# M8_AUX_CONN.net
KiCad netlist of a schematic drawn in Altium Designer
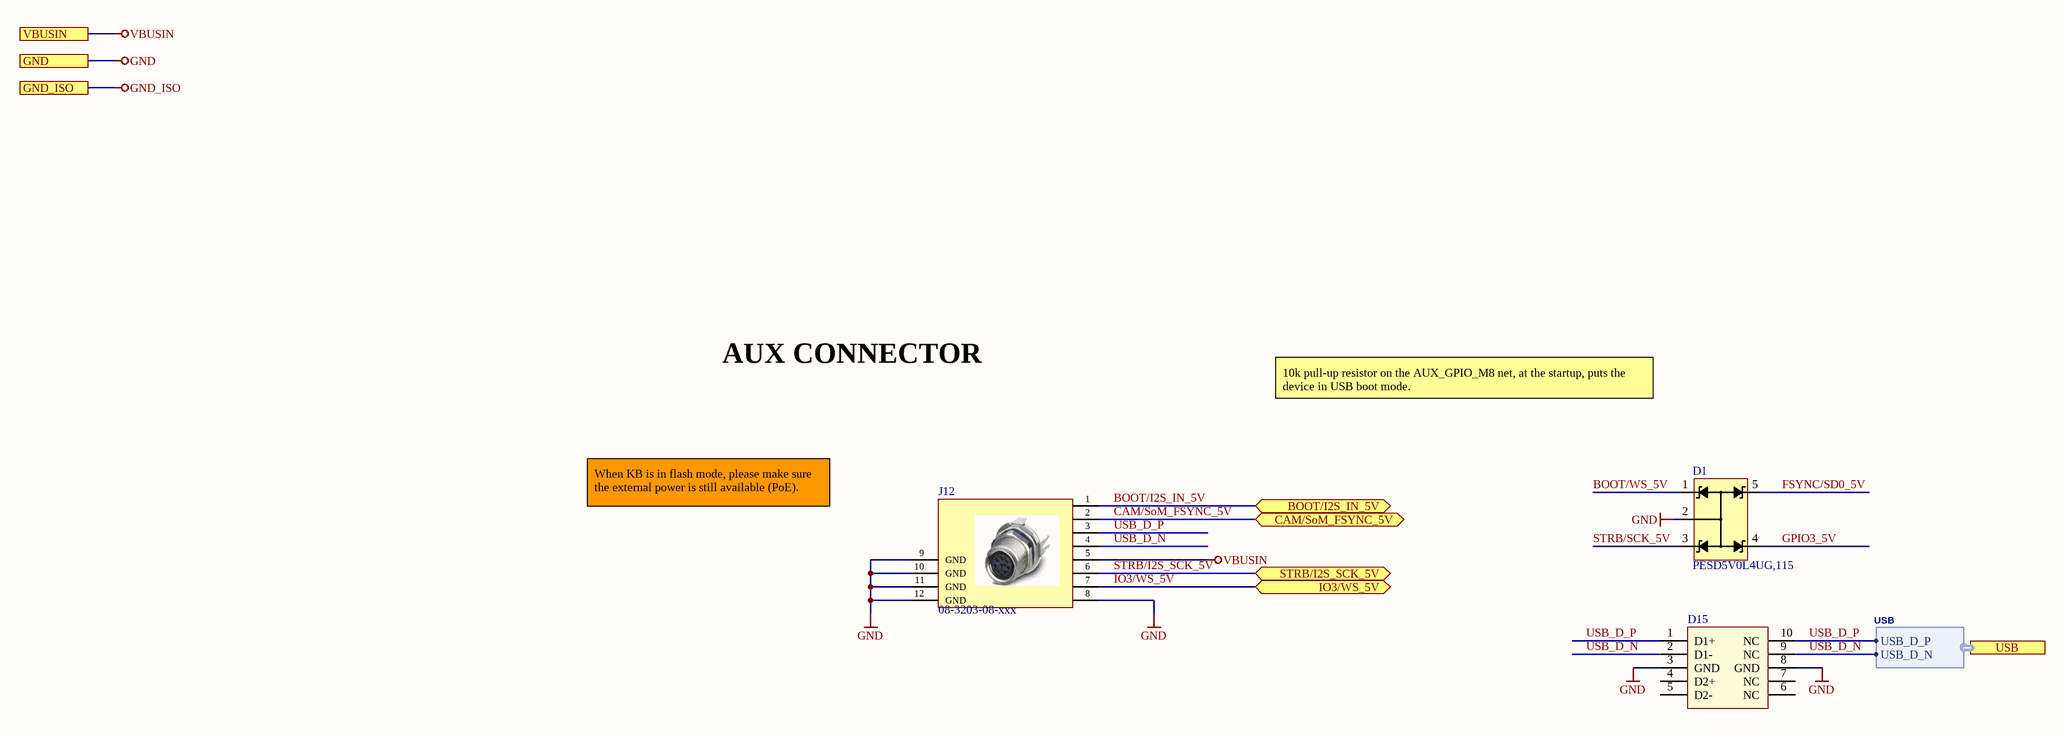
[diagram p0: M8_AUX_CONN.SchDoc]

(export (version "E")
  (design (tool "Eeschema 10.0.6"))
  (components
    (comp (ref "D1")
      (value "PESD5V0L4UG,115")
      (footprint "PESD3V3L4UG,115")
      (description "TVS DIODE 5V 12V 5TSSOP")
      (libsource (lib "Luxonis LLC") (part "PESD5V0L4UG,115"))
    )
    (comp (ref "D15")
      (value "TPD4EUSB30DQAR")
      (footprint "TPD4EUSB30DQAR")
      (description "TVS DIODE 5.5V 8V 10SON 8V Clamp 1A (8/20µs) Ipp Tvs Diode Surface Mount 10-USON (2.5x1)")
      (libsource (lib "Luxonis LLC") (part "TPD4EUSB30DQAR"))
    )
    (comp (ref "J12")
      (value "08-3203-08-xxx")
      (footprint "08-3203-08-XXX")
      (description "M8 Circular Connector")
      (libsource (lib "Luxonis LLC") (part "08-3203-08-xxx"))
    )
  )
  (nets
    (net (code "2") (name "/BOOT{slash}I2S_IN_5V") (class "Default")
      (node (ref "J12") (pin "1") (pinfunction "1_1") (pintype "passive"))
    )
    (net (code "3") (name "/BOOT{slash}WS_5V") (class "Default")
      (node (ref "D1") (pin "1") (pinfunction "1_1") (pintype "passive"))
    )
    (net (code "4") (name "/CAM{slash}SoM_FSYNC_5V") (class "Default")
      (node (ref "J12") (pin "2") (pinfunction "2_2") (pintype "passive"))
    )
    (net (code "5") (name "/FSYNC{slash}SD0_5V") (class "Default")
      (node (ref "D1") (pin "5") (pinfunction "5_5") (pintype "passive"))
    )
    (net (code "6") (name "/GPIO3_5V") (class "Default")
      (node (ref "D1") (pin "4") (pinfunction "4_4") (pintype "passive"))
    )
    (net (code "7") (name "/IO3{slash}WS_5V") (class "Default")
      (node (ref "J12") (pin "7") (pinfunction "7_7") (pintype "passive"))
    )
    (net (code "8") (name "/STRB{slash}I2S_SCK_5V") (class "Default")
      (node (ref "J12") (pin "6") (pinfunction "6_6") (pintype "passive"))
    )
    (net (code "9") (name "/STRB{slash}SCK_5V") (class "Default")
      (node (ref "D1") (pin "3") (pinfunction "3_3") (pintype "passive"))
    )
    (net (code "10") (name "/USB_D_N") (class "Default")
      (node (ref "D15") (pin "2") (pinfunction "D1-_2") (pintype "passive"))
      (node (ref "D15") (pin "9") (pinfunction "NC_9") (pintype "passive"))
      (node (ref "J12") (pin "4") (pinfunction "4_4") (pintype "passive"))
    )
    (net (code "11") (name "/USB_D_P") (class "Default")
      (node (ref "D15") (pin "1") (pinfunction "D1+_1") (pintype "passive"))
      (node (ref "D15") (pin "10") (pinfunction "NC_10") (pintype "passive"))
      (node (ref "J12") (pin "3") (pinfunction "3_3") (pintype "passive"))
    )
    (net (code "13") (name "GND") (class "Default")
      (node (ref "D1") (pin "2") (pinfunction "2_2") (pintype "passive"))
      (node (ref "D15") (pin "3") (pinfunction "GND_3") (pintype "passive"))
      (node (ref "D15") (pin "8") (pinfunction "GND_8") (pintype "passive"))
      (node (ref "J12") (pin "10") (pinfunction "GND_10") (pintype "passive"))
      (node (ref "J12") (pin "11") (pinfunction "GND_11") (pintype "passive"))
      (node (ref "J12") (pin "12") (pinfunction "GND_12") (pintype "passive"))
      (node (ref "J12") (pin "8") (pinfunction "8_8") (pintype "passive"))
      (node (ref "J12") (pin "9") (pinfunction "GND_9") (pintype "passive"))
    )
    (net (code "15") (name "VBUSIN") (class "Default")
      (node (ref "J12") (pin "5") (pinfunction "5_5") (pintype "passive"))
    )
    (net (code "16") (name "unconnected-(D15-D2+-Pad4)") (class "Default")
      (node (ref "D15") (pin "4") (pinfunction "D2+_4") (pintype "passive"))
    )
    (net (code "17") (name "unconnected-(D15-D2--Pad5)") (class "Default")
      (node (ref "D15") (pin "5") (pinfunction "D2-_5") (pintype "passive"))
    )
    (net (code "18") (name "unconnected-(D15-NC-Pad6)") (class "Default")
      (node (ref "D15") (pin "6") (pinfunction "NC_6") (pintype "passive"))
    )
    (net (code "19") (name "unconnected-(D15-NC-Pad7)") (class "Default")
      (node (ref "D15") (pin "7") (pinfunction "NC_7") (pintype "passive"))
    )
  )
)
